# SCH_HomeCon_2026-09-18.net
KiCad netlist of a schematic drawn in EasyEDA
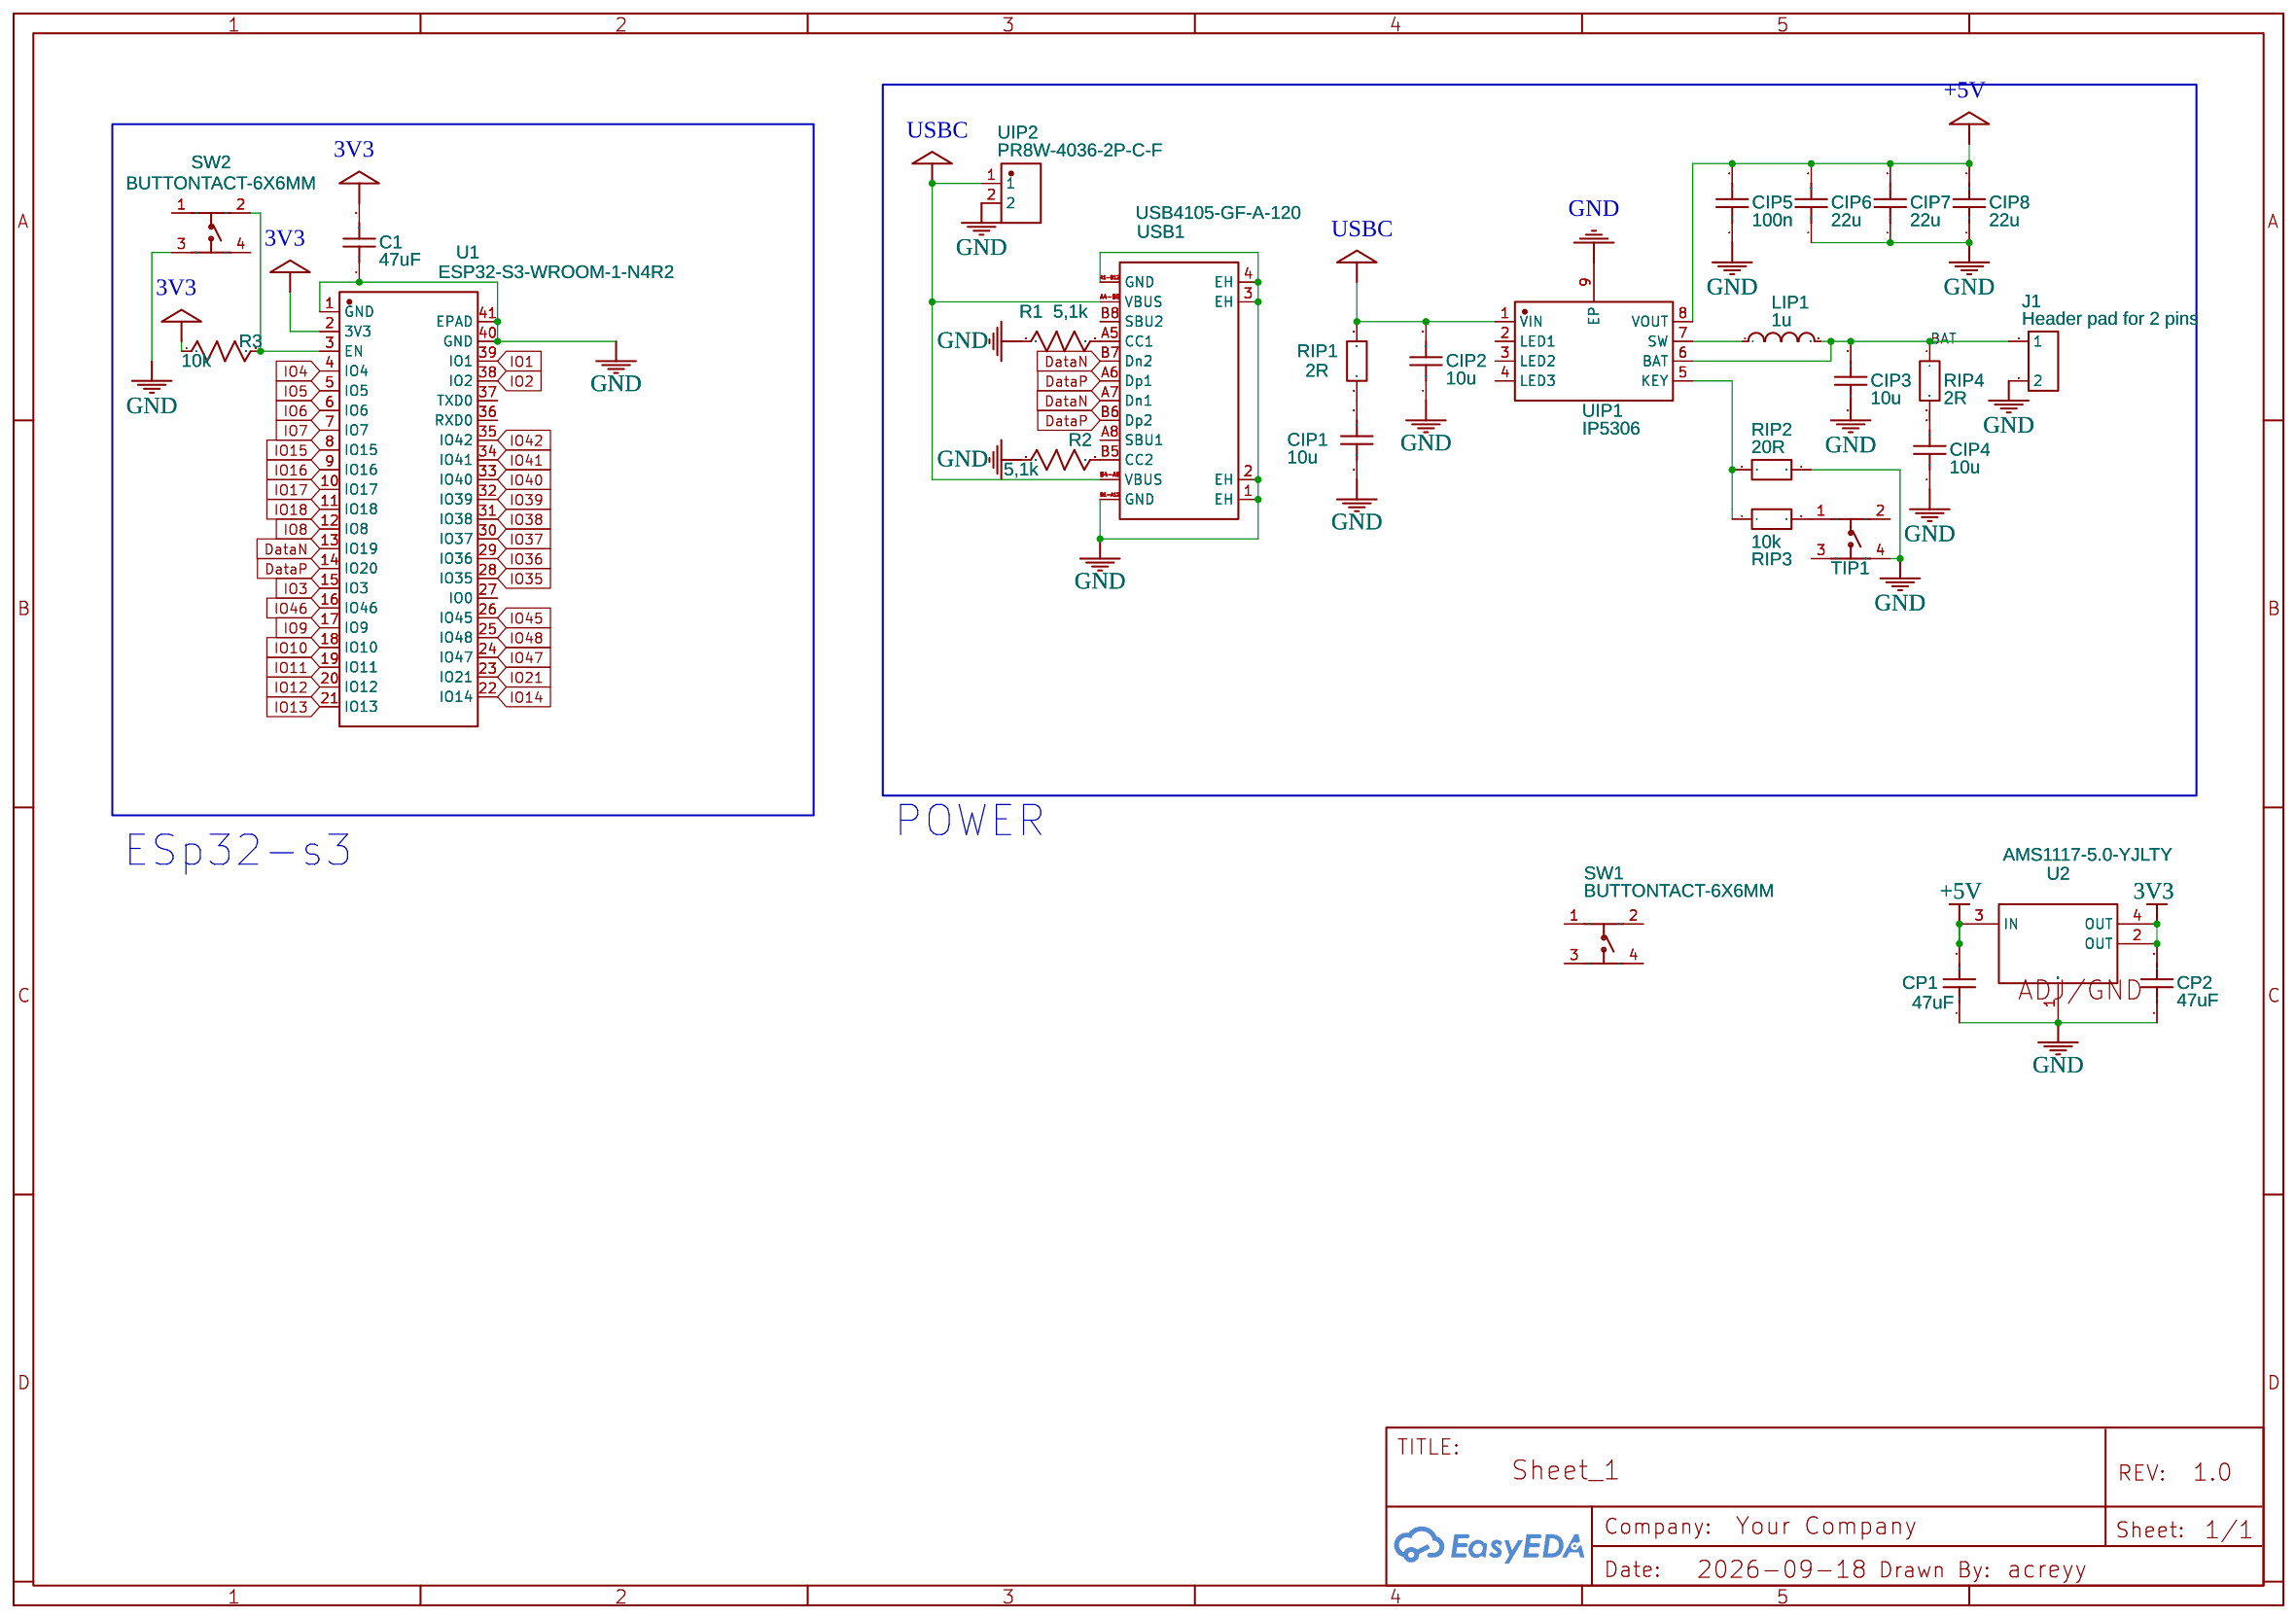
[diagram p0: schematic sheet]

(export (version "E")
  (design (tool "Eeschema 10.0.6"))
  (components
    (comp (ref "C1") (value "47uF") (libsource (lib "") (part "C_0805_US_2")))
    (comp (ref "CIP1") (value "10u") (libsource (lib "") (part "C_0805_US_1")))
    (comp (ref "CIP2") (value "10u") (libsource (lib "") (part "C_0805_US_1")))
    (comp (ref "CIP3") (value "10u") (libsource (lib "") (part "C_0805_US_1")))
    (comp (ref "CIP4") (value "10u") (libsource (lib "") (part "C_0805_US_1")))
    (comp (ref "CIP5") (value "100n") (libsource (lib "") (part "C_0805_US_1")))
    (comp (ref "CIP6") (value "22u") (libsource (lib "") (part "C_0805_US_1")))
    (comp (ref "CIP7") (value "22u") (libsource (lib "") (part "C_0805_US_1")))
    (comp (ref "CIP8") (value "22u") (libsource (lib "") (part "C_0805_US_1")))
    (comp (ref "CP1") (value "47uF") (libsource (lib "") (part "C_0805_US")))
    (comp (ref "CP2") (value "47uF") (libsource (lib "") (part "C_0805_US")))
    (comp (ref "J1")
      (value "Header pad for 2 pins")
      (fields
        (field (name "Manufacturer Part") "Female headerHDR1X8-2.54")
        (field (name "Manufacturer") "BOOMELE")
      )
      (libsource (lib "") (part "HEADER PAD 2X"))
    )
    (comp (ref "LIP1") (value "1u") (libsource (lib "") (part "L_AXIAL-0.4_US")))
    (comp (ref "R1") (value "5,1k") (libsource (lib "") (part "R_0805_US")))
    (comp (ref "R2") (value "5,1k") (libsource (lib "") (part "R_0805_US")))
    (comp (ref "R3") (value "10k") (libsource (lib "") (part "R_0805_US")))
    (comp (ref "RIP1") (value "2R") (libsource (lib "") (part "R_0603_EU_3")))
    (comp (ref "RIP2") (value "20R") (libsource (lib "") (part "R_0603_EU")))
    (comp (ref "RIP3") (value "10k") (libsource (lib "") (part "R_0603_EU_1")))
    (comp (ref "RIP4") (value "2R") (libsource (lib "") (part "R_0603_EU_2")))
    (comp (ref "SW1")
      (value "BUTTONTACT-6X6MM")
      (fields (field (name "Manufacturer Part") "Buttontact-6x6mm"))
      (libsource (lib "") (part "BUTTONTACT-6X6MM"))
    )
    (comp (ref "SW2")
      (value "BUTTONTACT-6X6MM")
      (fields (field (name "Manufacturer Part") "Buttontact-6x6mm"))
      (libsource (lib "") (part "BUTTONTACT-6X6MM"))
    )
    (comp (ref "TIP1")
      (value "BUTTONTACT-6X6MM")
      (fields (field (name "Manufacturer Part") "Buttontact-6x6mm"))
      (libsource (lib "") (part "BUTTONTACT-6X6MM_1"))
    )
    (comp (ref "U1")
      (value "ESP32-S3-WROOM-1-N4R2")
      (fields (field (name "Manufacturer") "ESPRESSIF(乐鑫)"))
      (libsource (lib "") (part "ESP32-S3-WROOM-1-N4R2"))
    )
    (comp (ref "U2") (value "AMS1117-5.0-YJLTY") (libsource (lib "") (part "AMS1117-5.0-YJLTY")))
    (comp (ref "UIP1")
      (value "IP5306")
      (fields (field (name "Manufacturer") "INJOINIC(英集芯)"))
      (libsource (lib "") (part "IP5306"))
    )
    (comp (ref "UIP2")
      (value "PR8W-4036-2P-C-F")
      (fields (field (name "Manufacturer") "SAMZO(三佐)"))
      (libsource (lib "") (part "PR8W-4036-2P-C-F"))
    )
    (comp (ref "USB1")
      (value "USB4105-GF-A-120")
      (fields (field (name "Manufacturer") "GCT"))
      (libsource (lib "") (part "USB4105-GF-A-120"))
    )
  )
  (nets
    (net (code "1") (name "+5V") (class "Default")
      (node (ref "CIP5") (pin "2") (pinfunction "2_2") (pintype "unspecified"))
      (node (ref "CIP6") (pin "2") (pinfunction "2_2") (pintype "unspecified"))
      (node (ref "CIP7") (pin "2") (pinfunction "2_2") (pintype "unspecified"))
      (node (ref "CIP8") (pin "2") (pinfunction "2_2") (pintype "unspecified"))
      (node (ref "CP1") (pin "2") (pinfunction "2_2") (pintype "unspecified"))
      (node (ref "U2") (pin "3") (pinfunction "IN_3") (pintype "passive"))
      (node (ref "UIP1") (pin "8") (pinfunction "VOUT_8") (pintype "unspecified"))
    )
    (net (code "2") (name "/BAT") (class "Default")
      (node (ref "CIP3") (pin "2") (pinfunction "2_2") (pintype "unspecified"))
      (node (ref "J1") (pin "1") (pinfunction "1_1") (pintype "unspecified"))
      (node (ref "LIP1") (pin "2") (pinfunction "2_2") (pintype "unspecified"))
      (node (ref "RIP4") (pin "1") (pinfunction "1_1") (pintype "unspecified"))
      (node (ref "UIP1") (pin "6") (pinfunction "BAT_6") (pintype "unspecified"))
    )
    (net (code "3") (name "3V3") (class "Default")
      (node (ref "C1") (pin "2") (pinfunction "2_2") (pintype "unspecified"))
      (node (ref "CP2") (pin "2") (pinfunction "2_2") (pintype "unspecified"))
      (node (ref "R3") (pin "1") (pinfunction "1_1") (pintype "unspecified"))
      (node (ref "U1") (pin "2") (pinfunction "3V3_2") (pintype "unspecified"))
      (node (ref "U2") (pin "2") (pinfunction "OUT_2") (pintype "passive"))
      (node (ref "U2") (pin "4") (pinfunction "OUT_4") (pintype "passive"))
    )
    (net (code "4") (name "DataN") (class "Default")
      (node (ref "U1") (pin "13") (pinfunction "IO19_13") (pintype "unspecified"))
      (node (ref "USB1") (pin "A7") (pinfunction "Dn1_A7") (pintype "unspecified"))
      (node (ref "USB1") (pin "B7") (pinfunction "Dn2_B7") (pintype "unspecified"))
    )
    (net (code "5") (name "DataP") (class "Default")
      (node (ref "U1") (pin "14") (pinfunction "IO20_14") (pintype "unspecified"))
      (node (ref "USB1") (pin "A6") (pinfunction "Dp1_A6") (pintype "unspecified"))
      (node (ref "USB1") (pin "B6") (pinfunction "Dp2_B6") (pintype "unspecified"))
    )
    (net (code "6") (name "GND") (class "Default")
      (node (ref "C1") (pin "1") (pinfunction "1_1") (pintype "unspecified"))
      (node (ref "CIP1") (pin "1") (pinfunction "1_1") (pintype "unspecified"))
      (node (ref "CIP2") (pin "1") (pinfunction "1_1") (pintype "unspecified"))
      (node (ref "CIP4") (pin "1") (pinfunction "1_1") (pintype "unspecified"))
      (node (ref "CIP5") (pin "1") (pinfunction "1_1") (pintype "unspecified"))
      (node (ref "CIP6") (pin "1") (pinfunction "1_1") (pintype "unspecified"))
      (node (ref "CIP7") (pin "1") (pinfunction "1_1") (pintype "unspecified"))
      (node (ref "CIP8") (pin "1") (pinfunction "1_1") (pintype "unspecified"))
      (node (ref "CP1") (pin "1") (pinfunction "1_1") (pintype "unspecified"))
      (node (ref "CP2") (pin "1") (pinfunction "1_1") (pintype "unspecified"))
      (node (ref "J1") (pin "2") (pinfunction "2_2") (pintype "unspecified"))
      (node (ref "R1") (pin "1") (pinfunction "1_1") (pintype "unspecified"))
      (node (ref "R2") (pin "1") (pinfunction "1_1") (pintype "unspecified"))
      (node (ref "RIP2") (pin "1") (pinfunction "1_1") (pintype "unspecified"))
      (node (ref "SW2") (pin "3") (pinfunction "C_3") (pintype "unspecified"))
      (node (ref "TIP1") (pin "4") (pinfunction "D_4") (pintype "unspecified"))
      (node (ref "U1") (pin "1") (pinfunction "GND_1") (pintype "unspecified"))
      (node (ref "U1") (pin "40") (pinfunction "GND_40") (pintype "unspecified"))
      (node (ref "U1") (pin "41") (pinfunction "EPAD_41") (pintype "unspecified"))
      (node (ref "U2") (pin "1") (pinfunction "ADJ/GND_1") (pintype "passive"))
      (node (ref "UIP1") (pin "9") (pinfunction "EP_9") (pintype "unspecified"))
      (node (ref "UIP2") (pin "2") (pinfunction "2_2") (pintype "unspecified"))
      (node (ref "USB1") (pin "1") (pinfunction "EH_1") (pintype "unspecified"))
      (node (ref "USB1") (pin "2") (pinfunction "EH_2") (pintype "unspecified"))
      (node (ref "USB1") (pin "3") (pinfunction "EH_3") (pintype "unspecified"))
      (node (ref "USB1") (pin "4") (pinfunction "EH_4") (pintype "unspecified"))
      (node (ref "USB1") (pin "A1-B12") (pinfunction "GND_A1-B12") (pintype "unspecified"))
      (node (ref "USB1") (pin "B1-A12") (pinfunction "GND_B1-A12") (pintype "unspecified"))
    )
    (net (code "7") (name "IO1") (class "Default")
      (node (ref "U1") (pin "39") (pinfunction "IO1_39") (pintype "unspecified"))
    )
    (net (code "8") (name "IO2") (class "Default")
      (node (ref "U1") (pin "38") (pinfunction "IO2_38") (pintype "unspecified"))
    )
    (net (code "9") (name "IO3") (class "Default")
      (node (ref "U1") (pin "15") (pinfunction "IO3_15") (pintype "unspecified"))
    )
    (net (code "10") (name "IO4") (class "Default")
      (node (ref "U1") (pin "4") (pinfunction "IO4_4") (pintype "unspecified"))
    )
    (net (code "11") (name "IO5") (class "Default")
      (node (ref "U1") (pin "5") (pinfunction "IO5_5") (pintype "unspecified"))
    )
    (net (code "12") (name "IO6") (class "Default")
      (node (ref "U1") (pin "6") (pinfunction "IO6_6") (pintype "unspecified"))
    )
    (net (code "13") (name "IO7") (class "Default")
      (node (ref "U1") (pin "7") (pinfunction "IO7_7") (pintype "unspecified"))
    )
    (net (code "14") (name "IO8") (class "Default")
      (node (ref "U1") (pin "12") (pinfunction "IO8_12") (pintype "unspecified"))
    )
    (net (code "15") (name "IO9") (class "Default")
      (node (ref "U1") (pin "17") (pinfunction "IO9_17") (pintype "unspecified"))
    )
    (net (code "16") (name "IO10") (class "Default")
      (node (ref "U1") (pin "18") (pinfunction "IO10_18") (pintype "unspecified"))
    )
    (net (code "17") (name "IO11") (class "Default")
      (node (ref "U1") (pin "19") (pinfunction "IO11_19") (pintype "unspecified"))
    )
    (net (code "18") (name "IO12") (class "Default")
      (node (ref "U1") (pin "20") (pinfunction "IO12_20") (pintype "unspecified"))
    )
    (net (code "19") (name "IO13") (class "Default")
      (node (ref "U1") (pin "21") (pinfunction "IO13_21") (pintype "unspecified"))
    )
    (net (code "20") (name "IO14") (class "Default")
      (node (ref "U1") (pin "22") (pinfunction "IO14_22") (pintype "unspecified"))
    )
    (net (code "21") (name "IO15") (class "Default")
      (node (ref "U1") (pin "8") (pinfunction "IO15_8") (pintype "unspecified"))
    )
    (net (code "22") (name "IO16") (class "Default")
      (node (ref "U1") (pin "9") (pinfunction "IO16_9") (pintype "unspecified"))
    )
    (net (code "23") (name "IO17") (class "Default")
      (node (ref "U1") (pin "10") (pinfunction "IO17_10") (pintype "unspecified"))
    )
    (net (code "24") (name "IO18") (class "Default")
      (node (ref "U1") (pin "11") (pinfunction "IO18_11") (pintype "unspecified"))
    )
    (net (code "25") (name "IO21") (class "Default")
      (node (ref "U1") (pin "23") (pinfunction "IO21_23") (pintype "unspecified"))
    )
    (net (code "26") (name "IO35") (class "Default")
      (node (ref "U1") (pin "28") (pinfunction "IO35_28") (pintype "unspecified"))
    )
    (net (code "27") (name "IO36") (class "Default")
      (node (ref "U1") (pin "29") (pinfunction "IO36_29") (pintype "unspecified"))
    )
    (net (code "28") (name "IO37") (class "Default")
      (node (ref "U1") (pin "30") (pinfunction "IO37_30") (pintype "unspecified"))
    )
    (net (code "29") (name "IO38") (class "Default")
      (node (ref "U1") (pin "31") (pinfunction "IO38_31") (pintype "unspecified"))
    )
    (net (code "30") (name "IO39") (class "Default")
      (node (ref "U1") (pin "32") (pinfunction "IO39_32") (pintype "unspecified"))
    )
    (net (code "31") (name "IO40") (class "Default")
      (node (ref "U1") (pin "33") (pinfunction "IO40_33") (pintype "unspecified"))
    )
    (net (code "32") (name "IO41") (class "Default")
      (node (ref "U1") (pin "34") (pinfunction "IO41_34") (pintype "unspecified"))
    )
    (net (code "33") (name "IO42") (class "Default")
      (node (ref "U1") (pin "35") (pinfunction "IO42_35") (pintype "unspecified"))
    )
    (net (code "34") (name "IO45") (class "Default")
      (node (ref "U1") (pin "26") (pinfunction "IO45_26") (pintype "unspecified"))
    )
    (net (code "35") (name "IO46") (class "Default")
      (node (ref "U1") (pin "16") (pinfunction "IO46_16") (pintype "unspecified"))
    )
    (net (code "36") (name "IO47") (class "Default")
      (node (ref "U1") (pin "24") (pinfunction "IO47_24") (pintype "unspecified"))
    )
    (net (code "37") (name "IO48") (class "Default")
      (node (ref "U1") (pin "25") (pinfunction "IO48_25") (pintype "unspecified"))
    )
    (net (code "38") (name "Net-(CIP1-Pad2)") (class "Default")
      (node (ref "CIP1") (pin "2") (pinfunction "2_2") (pintype "unspecified"))
      (node (ref "RIP1") (pin "1") (pinfunction "1_1") (pintype "unspecified"))
    )
    (net (code "39") (name "Net-(SW2-B)") (class "Default")
      (node (ref "R3") (pin "2") (pinfunction "2_2") (pintype "unspecified"))
      (node (ref "SW2") (pin "2") (pinfunction "B_2") (pintype "unspecified"))
      (node (ref "U1") (pin "3") (pinfunction "EN_3") (pintype "unspecified"))
    )
    (net (code "40") (name "Net-(TIP1-A)") (class "Default")
      (node (ref "RIP3") (pin "2") (pinfunction "2_2") (pintype "unspecified"))
      (node (ref "TIP1") (pin "1") (pinfunction "A_1") (pintype "unspecified"))
    )
    (net (code "41") (name "Net-(UIP1-KEY)") (class "Default")
      (node (ref "RIP2") (pin "2") (pinfunction "2_2") (pintype "unspecified"))
      (node (ref "RIP3") (pin "1") (pinfunction "1_1") (pintype "unspecified"))
      (node (ref "UIP1") (pin "5") (pinfunction "KEY_5") (pintype "unspecified"))
    )
    (net (code "42") (name "Net-(UIP1-SW)") (class "Default")
      (node (ref "LIP1") (pin "1") (pinfunction "1_1") (pintype "unspecified"))
      (node (ref "UIP1") (pin "7") (pinfunction "SW_7") (pintype "unspecified"))
    )
    (net (code "43") (name "Net-(USB1-CC1)") (class "Default")
      (node (ref "R1") (pin "2") (pinfunction "2_2") (pintype "unspecified"))
      (node (ref "USB1") (pin "A5") (pinfunction "CC1_A5") (pintype "unspecified"))
    )
    (net (code "44") (name "Net-(USB1-CC2)") (class "Default")
      (node (ref "R2") (pin "2") (pinfunction "2_2") (pintype "unspecified"))
      (node (ref "USB1") (pin "B5") (pinfunction "CC2_B5") (pintype "unspecified"))
    )
    (net (code "45") (name "USBC") (class "Default")
      (node (ref "CIP2") (pin "2") (pinfunction "2_2") (pintype "unspecified"))
      (node (ref "RIP1") (pin "2") (pinfunction "2_2") (pintype "unspecified"))
      (node (ref "UIP1") (pin "1") (pinfunction "VIN_1") (pintype "unspecified"))
      (node (ref "UIP2") (pin "1") (pinfunction "1_1") (pintype "unspecified"))
      (node (ref "USB1") (pin "A4-B9") (pinfunction "VBUS_A4-B9") (pintype "unspecified"))
      (node (ref "USB1") (pin "B4-A9") (pinfunction "VBUS_B4-A9") (pintype "unspecified"))
    )
    (net (code "46") (name "unconnected-(CIP3-Pad1)") (class "Default")
      (node (ref "CIP3") (pin "1") (pinfunction "1_1") (pintype "unspecified"))
    )
    (net (code "47") (name "unconnected-(CIP4-Pad2)") (class "Default")
      (node (ref "CIP4") (pin "2") (pinfunction "2_2") (pintype "unspecified"))
    )
    (net (code "48") (name "unconnected-(RIP4-Pad2)") (class "Default")
      (node (ref "RIP4") (pin "2") (pinfunction "2_2") (pintype "unspecified"))
    )
    (net (code "49") (name "unconnected-(SW1-A-Pad1)") (class "Default")
      (node (ref "SW1") (pin "1") (pinfunction "A_1") (pintype "unspecified"))
    )
    (net (code "50") (name "unconnected-(SW1-B-Pad2)") (class "Default")
      (node (ref "SW1") (pin "2") (pinfunction "B_2") (pintype "unspecified"))
    )
    (net (code "51") (name "unconnected-(SW1-C-Pad3)") (class "Default")
      (node (ref "SW1") (pin "3") (pinfunction "C_3") (pintype "unspecified"))
    )
    (net (code "52") (name "unconnected-(SW1-D-Pad4)") (class "Default")
      (node (ref "SW1") (pin "4") (pinfunction "D_4") (pintype "unspecified"))
    )
    (net (code "53") (name "unconnected-(SW2-A-Pad1)") (class "Default")
      (node (ref "SW2") (pin "1") (pinfunction "A_1") (pintype "unspecified"))
    )
    (net (code "54") (name "unconnected-(SW2-D-Pad4)") (class "Default")
      (node (ref "SW2") (pin "4") (pinfunction "D_4") (pintype "unspecified"))
    )
    (net (code "55") (name "unconnected-(TIP1-B-Pad2)") (class "Default")
      (node (ref "TIP1") (pin "2") (pinfunction "B_2") (pintype "unspecified"))
    )
    (net (code "56") (name "unconnected-(TIP1-C-Pad3)") (class "Default")
      (node (ref "TIP1") (pin "3") (pinfunction "C_3") (pintype "unspecified"))
    )
    (net (code "57") (name "unconnected-(U1-IO0-Pad27)") (class "Default")
      (node (ref "U1") (pin "27") (pinfunction "IO0_27") (pintype "unspecified"))
    )
    (net (code "58") (name "unconnected-(U1-RXD0-Pad36)") (class "Default")
      (node (ref "U1") (pin "36") (pinfunction "RXD0_36") (pintype "unspecified"))
    )
    (net (code "59") (name "unconnected-(U1-TXD0-Pad37)") (class "Default")
      (node (ref "U1") (pin "37") (pinfunction "TXD0_37") (pintype "unspecified"))
    )
    (net (code "60") (name "unconnected-(UIP1-LED1-Pad2)") (class "Default")
      (node (ref "UIP1") (pin "2") (pinfunction "LED1_2") (pintype "unspecified"))
    )
    (net (code "61") (name "unconnected-(UIP1-LED2-Pad3)") (class "Default")
      (node (ref "UIP1") (pin "3") (pinfunction "LED2_3") (pintype "unspecified"))
    )
    (net (code "62") (name "unconnected-(UIP1-LED3-Pad4)") (class "Default")
      (node (ref "UIP1") (pin "4") (pinfunction "LED3_4") (pintype "unspecified"))
    )
    (net (code "63") (name "unconnected-(USB1-SBU1-PadA8)") (class "Default")
      (node (ref "USB1") (pin "A8") (pinfunction "SBU1_A8") (pintype "unspecified"))
    )
    (net (code "64") (name "unconnected-(USB1-SBU2-PadB8)") (class "Default")
      (node (ref "USB1") (pin "B8") (pinfunction "SBU2_B8") (pintype "unspecified"))
    )
  )
)
